# OSD_Mixer.net
KiCad netlist of a schematic drawn in EAGLE
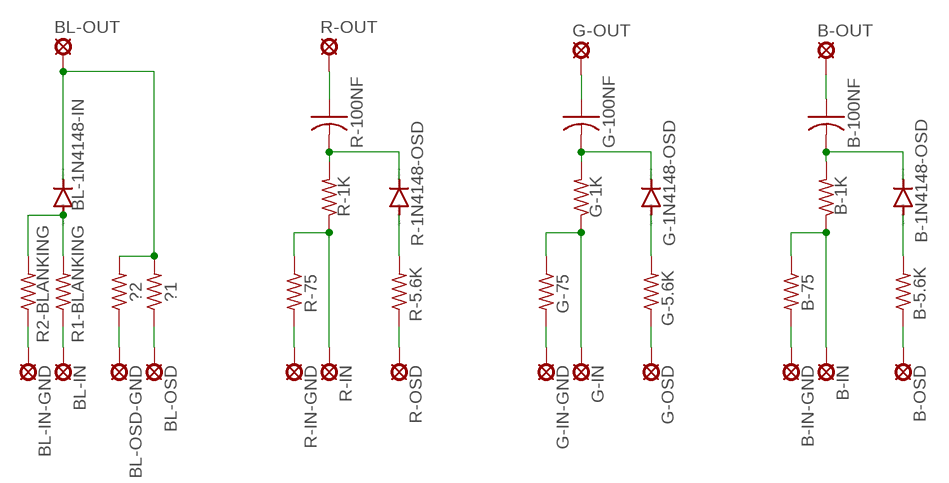
[diagram p0: schematic, sheet 1]

(export (version "E")
  (design (tool "Eeschema 10.0.6"))
  (components
    (comp (ref "?1")
      (value "R-US_0204/2V")
      (footprint "eagle-import:0204V")
      (libsource (lib "eagle-import") (part "R-US_0204/2V"))
    )
    (comp (ref "?2")
      (value "R-US_0204/2V")
      (footprint "eagle-import:0204V")
      (libsource (lib "eagle-import") (part "R-US_0204/2V"))
    )
    (comp (ref "B-1K")
      (value "R-US_0204/2V")
      (footprint "eagle-import:0204V")
      (libsource (lib "eagle-import") (part "R-US_0204/2V"))
    )
    (comp (ref "B-1N4148-OSD")
      (value "1N4148DO35-7")
      (footprint "eagle-import:DO35-7")
      (libsource (lib "eagle-import") (part "1N4148DO35-7"))
    )
    (comp (ref "B-5.6K")
      (value "R-US_0204/2V")
      (footprint "eagle-import:0204V")
      (libsource (lib "eagle-import") (part "R-US_0204/2V"))
    )
    (comp (ref "B-75")
      (value "R-US_0204/2V")
      (footprint "eagle-import:0204V")
      (libsource (lib "eagle-import") (part "R-US_0204/2V"))
    )
    (comp (ref "B-100NF")
      (value "C-US025-024X044")
      (footprint "eagle-import:C025-024X044")
      (libsource (lib "eagle-import") (part "C-US025-024X044"))
    )
    (comp (ref "B-IN")
      (value "SE14")
      (footprint "eagle-import:SE14")
      (libsource (lib "eagle-import") (part "SE14"))
    )
    (comp (ref "B-IN-GND")
      (value "SE14")
      (footprint "eagle-import:SE14")
      (libsource (lib "eagle-import") (part "SE14"))
    )
    (comp (ref "B-OSD")
      (value "SE14")
      (footprint "eagle-import:SE14")
      (libsource (lib "eagle-import") (part "SE14"))
    )
    (comp (ref "B-OUT")
      (value "SE14")
      (footprint "eagle-import:SE14")
      (libsource (lib "eagle-import") (part "SE14"))
    )
    (comp (ref "BL-1N4148-IN")
      (value "1N4148DO35-7")
      (footprint "eagle-import:DO35-7")
      (libsource (lib "eagle-import") (part "1N4148DO35-7"))
    )
    (comp (ref "BL-IN")
      (value "SE14")
      (footprint "eagle-import:SE14")
      (libsource (lib "eagle-import") (part "SE14"))
    )
    (comp (ref "BL-IN-GND")
      (value "SE14")
      (footprint "eagle-import:SE14")
      (libsource (lib "eagle-import") (part "SE14"))
    )
    (comp (ref "BL-OSD")
      (value "SE14")
      (footprint "eagle-import:SE14")
      (libsource (lib "eagle-import") (part "SE14"))
    )
    (comp (ref "BL-OSD-GND")
      (value "SE14")
      (footprint "eagle-import:SE14")
      (libsource (lib "eagle-import") (part "SE14"))
    )
    (comp (ref "BL-OUT")
      (value "SE14")
      (footprint "eagle-import:SE14")
      (libsource (lib "eagle-import") (part "SE14"))
    )
    (comp (ref "G-1K")
      (value "R-US_0204/2V")
      (footprint "eagle-import:0204V")
      (libsource (lib "eagle-import") (part "R-US_0204/2V"))
    )
    (comp (ref "G-1N4148-OSD")
      (value "1N4148DO35-7")
      (footprint "eagle-import:DO35-7")
      (libsource (lib "eagle-import") (part "1N4148DO35-7"))
    )
    (comp (ref "G-5.6K")
      (value "R-US_0204/2V")
      (footprint "eagle-import:0204V")
      (libsource (lib "eagle-import") (part "R-US_0204/2V"))
    )
    (comp (ref "G-75")
      (value "R-US_0204/2V")
      (footprint "eagle-import:0204V")
      (libsource (lib "eagle-import") (part "R-US_0204/2V"))
    )
    (comp (ref "G-100NF")
      (value "C-US025-024X044")
      (footprint "eagle-import:C025-024X044")
      (libsource (lib "eagle-import") (part "C-US025-024X044"))
    )
    (comp (ref "G-IN")
      (value "SE14")
      (footprint "eagle-import:SE14")
      (libsource (lib "eagle-import") (part "SE14"))
    )
    (comp (ref "G-IN-GND")
      (value "SE14")
      (footprint "eagle-import:SE14")
      (libsource (lib "eagle-import") (part "SE14"))
    )
    (comp (ref "G-OSD")
      (value "SE14")
      (footprint "eagle-import:SE14")
      (libsource (lib "eagle-import") (part "SE14"))
    )
    (comp (ref "G-OUT")
      (value "SE14")
      (footprint "eagle-import:SE14")
      (libsource (lib "eagle-import") (part "SE14"))
    )
    (comp (ref "R-1K")
      (value "R-US_0204/2V")
      (footprint "eagle-import:0204V")
      (libsource (lib "eagle-import") (part "R-US_0204/2V"))
    )
    (comp (ref "R-1N4148-OSD")
      (value "1N4148DO35-7")
      (footprint "eagle-import:DO35-7")
      (libsource (lib "eagle-import") (part "1N4148DO35-7"))
    )
    (comp (ref "R-5.6K")
      (value "R-US_0204/2V")
      (footprint "eagle-import:0204V")
      (libsource (lib "eagle-import") (part "R-US_0204/2V"))
    )
    (comp (ref "R-75")
      (value "R-US_0204/2V")
      (footprint "eagle-import:0204V")
      (libsource (lib "eagle-import") (part "R-US_0204/2V"))
    )
    (comp (ref "R-100NF")
      (value "C-US025-024X044")
      (footprint "eagle-import:C025-024X044")
      (libsource (lib "eagle-import") (part "C-US025-024X044"))
    )
    (comp (ref "R-IN")
      (value "SE14")
      (footprint "eagle-import:SE14")
      (libsource (lib "eagle-import") (part "SE14"))
    )
    (comp (ref "R-IN-GND")
      (value "SE14")
      (footprint "eagle-import:SE14")
      (libsource (lib "eagle-import") (part "SE14"))
    )
    (comp (ref "R-OSD")
      (value "SE14")
      (footprint "eagle-import:SE14")
      (libsource (lib "eagle-import") (part "SE14"))
    )
    (comp (ref "R-OUT")
      (value "SE14")
      (footprint "eagle-import:SE14")
      (libsource (lib "eagle-import") (part "SE14"))
    )
    (comp (ref "R1-BLANKING")
      (value "R-US_0204/2V")
      (footprint "eagle-import:0204V")
      (libsource (lib "eagle-import") (part "R-US_0204/2V"))
    )
    (comp (ref "R2-BLANKING")
      (value "R-US_0204/2V")
      (footprint "eagle-import:0204V")
      (libsource (lib "eagle-import") (part "R-US_0204/2V"))
    )
  )
  (nets
    (net (code "1") (name "Net-(?1-Pad1)") (class "Default")
      (node (ref "?1") (pin "1") (pinfunction "1_1") (pintype "passive"))
      (node (ref "BL-OSD") (pin "MP") (pinfunction "MP_MP") (pintype "passive"))
    )
    (net (code "2") (name "Net-(?1-Pad2)") (class "Default")
      (node (ref "?1") (pin "2") (pinfunction "2_2") (pintype "passive"))
      (node (ref "?2") (pin "2") (pinfunction "2_2") (pintype "passive"))
      (node (ref "BL-1N4148-IN") (pin "C") (pinfunction "C_C") (pintype "passive"))
      (node (ref "BL-OUT") (pin "MP") (pinfunction "MP_MP") (pintype "passive"))
    )
    (net (code "3") (name "Net-(?2-Pad1)") (class "Default")
      (node (ref "?2") (pin "1") (pinfunction "1_1") (pintype "passive"))
      (node (ref "BL-OSD-GND") (pin "MP") (pinfunction "MP_MP") (pintype "passive"))
    )
    (net (code "4") (name "Net-(B-1K-Pad1)") (class "Default")
      (node (ref "B-1K") (pin "1") (pinfunction "1_1") (pintype "passive"))
      (node (ref "B-75") (pin "1") (pinfunction "1_1") (pintype "passive"))
      (node (ref "B-IN") (pin "MP") (pinfunction "MP_MP") (pintype "passive"))
    )
    (net (code "5") (name "Net-(B-1N4148-OSD-PadA)") (class "Default")
      (node (ref "B-1N4148-OSD") (pin "A") (pinfunction "A_A") (pintype "passive"))
      (node (ref "B-5.6K") (pin "2") (pinfunction "2_2") (pintype "passive"))
    )
    (net (code "6") (name "Net-(B-5.6K-Pad1)") (class "Default")
      (node (ref "B-5.6K") (pin "1") (pinfunction "1_1") (pintype "passive"))
      (node (ref "B-OSD") (pin "MP") (pinfunction "MP_MP") (pintype "passive"))
    )
    (net (code "7") (name "Net-(B-75-Pad2)") (class "Default")
      (node (ref "B-75") (pin "2") (pinfunction "2_2") (pintype "passive"))
      (node (ref "B-IN-GND") (pin "MP") (pinfunction "MP_MP") (pintype "passive"))
    )
    (net (code "8") (name "Net-(B-100NF-Pad1)") (class "Default")
      (node (ref "B-100NF") (pin "1") (pinfunction "1_1") (pintype "passive"))
      (node (ref "B-OUT") (pin "MP") (pinfunction "MP_MP") (pintype "passive"))
    )
    (net (code "9") (name "Net-(B-100NF-Pad2)") (class "Default")
      (node (ref "B-100NF") (pin "2") (pinfunction "2_2") (pintype "passive"))
      (node (ref "B-1K") (pin "2") (pinfunction "2_2") (pintype "passive"))
      (node (ref "B-1N4148-OSD") (pin "C") (pinfunction "C_C") (pintype "passive"))
    )
    (net (code "10") (name "Net-(BL-1N4148-IN-PadA)") (class "Default")
      (node (ref "BL-1N4148-IN") (pin "A") (pinfunction "A_A") (pintype "passive"))
      (node (ref "R1-BLANKING") (pin "2") (pinfunction "2_2") (pintype "passive"))
      (node (ref "R2-BLANKING") (pin "2") (pinfunction "2_2") (pintype "passive"))
    )
    (net (code "11") (name "Net-(BL-IN-GND-PadMP)") (class "Default")
      (node (ref "BL-IN-GND") (pin "MP") (pinfunction "MP_MP") (pintype "passive"))
      (node (ref "R2-BLANKING") (pin "1") (pinfunction "1_1") (pintype "passive"))
    )
    (net (code "12") (name "Net-(BL-IN-PadMP)") (class "Default")
      (node (ref "BL-IN") (pin "MP") (pinfunction "MP_MP") (pintype "passive"))
      (node (ref "R1-BLANKING") (pin "1") (pinfunction "1_1") (pintype "passive"))
    )
    (net (code "13") (name "Net-(G-1K-Pad1)") (class "Default")
      (node (ref "G-1K") (pin "1") (pinfunction "1_1") (pintype "passive"))
      (node (ref "G-75") (pin "1") (pinfunction "1_1") (pintype "passive"))
      (node (ref "G-IN") (pin "MP") (pinfunction "MP_MP") (pintype "passive"))
    )
    (net (code "14") (name "Net-(G-1N4148-OSD-PadA)") (class "Default")
      (node (ref "G-1N4148-OSD") (pin "A") (pinfunction "A_A") (pintype "passive"))
      (node (ref "G-5.6K") (pin "2") (pinfunction "2_2") (pintype "passive"))
    )
    (net (code "15") (name "Net-(G-5.6K-Pad1)") (class "Default")
      (node (ref "G-5.6K") (pin "1") (pinfunction "1_1") (pintype "passive"))
      (node (ref "G-OSD") (pin "MP") (pinfunction "MP_MP") (pintype "passive"))
    )
    (net (code "16") (name "Net-(G-75-Pad2)") (class "Default")
      (node (ref "G-75") (pin "2") (pinfunction "2_2") (pintype "passive"))
      (node (ref "G-IN-GND") (pin "MP") (pinfunction "MP_MP") (pintype "passive"))
    )
    (net (code "17") (name "Net-(G-100NF-Pad1)") (class "Default")
      (node (ref "G-100NF") (pin "1") (pinfunction "1_1") (pintype "passive"))
      (node (ref "G-OUT") (pin "MP") (pinfunction "MP_MP") (pintype "passive"))
    )
    (net (code "18") (name "Net-(G-100NF-Pad2)") (class "Default")
      (node (ref "G-100NF") (pin "2") (pinfunction "2_2") (pintype "passive"))
      (node (ref "G-1K") (pin "2") (pinfunction "2_2") (pintype "passive"))
      (node (ref "G-1N4148-OSD") (pin "C") (pinfunction "C_C") (pintype "passive"))
    )
    (net (code "19") (name "Net-(R-1K-Pad1)") (class "Default")
      (node (ref "R-1K") (pin "1") (pinfunction "1_1") (pintype "passive"))
      (node (ref "R-75") (pin "1") (pinfunction "1_1") (pintype "passive"))
      (node (ref "R-IN") (pin "MP") (pinfunction "MP_MP") (pintype "passive"))
    )
    (net (code "20") (name "Net-(R-1N4148-OSD-PadA)") (class "Default")
      (node (ref "R-1N4148-OSD") (pin "A") (pinfunction "A_A") (pintype "passive"))
      (node (ref "R-5.6K") (pin "2") (pinfunction "2_2") (pintype "passive"))
    )
    (net (code "21") (name "Net-(R-5.6K-Pad1)") (class "Default")
      (node (ref "R-5.6K") (pin "1") (pinfunction "1_1") (pintype "passive"))
      (node (ref "R-OSD") (pin "MP") (pinfunction "MP_MP") (pintype "passive"))
    )
    (net (code "22") (name "Net-(R-75-Pad2)") (class "Default")
      (node (ref "R-75") (pin "2") (pinfunction "2_2") (pintype "passive"))
      (node (ref "R-IN-GND") (pin "MP") (pinfunction "MP_MP") (pintype "passive"))
    )
    (net (code "23") (name "Net-(R-100NF-Pad1)") (class "Default")
      (node (ref "R-100NF") (pin "1") (pinfunction "1_1") (pintype "passive"))
      (node (ref "R-OUT") (pin "MP") (pinfunction "MP_MP") (pintype "passive"))
    )
    (net (code "24") (name "Net-(R-100NF-Pad2)") (class "Default")
      (node (ref "R-100NF") (pin "2") (pinfunction "2_2") (pintype "passive"))
      (node (ref "R-1K") (pin "2") (pinfunction "2_2") (pintype "passive"))
      (node (ref "R-1N4148-OSD") (pin "C") (pinfunction "C_C") (pintype "passive"))
    )
  )
)
